# percepcao_externa_comunicacao.net
KiCad netlist of a schematic drawn in Altium Designer
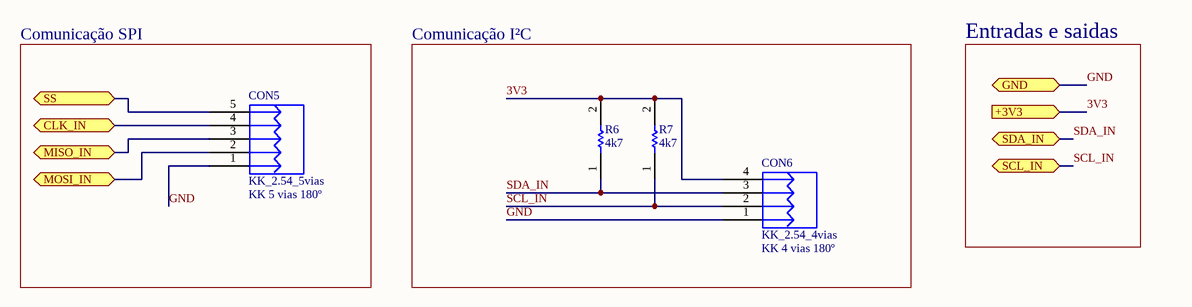
[diagram p0: percepcao_externa_comunicacao.SchDoc]

(export (version "E")
  (design (tool "Eeschema 10.0.6"))
  (components
    (comp (ref "CON5")
      (value "KK_2.54_5vias")
      (footprint "KK_5vias_180°")
      (description "Conector KK 2.54mm 5 vias")
      (fields (field (name "VALOR") "KK 5 vias 180º"))
      (libsource (lib "Sinaliza玢o_Official") (part "KK_2.54_5vias"))
    )
    (comp (ref "CON6")
      (value "KK_2.54_4vias")
      (footprint "KK_4vias_180°")
      (description "Conector KK 2.54mm 4 vias")
      (fields (field (name "VALOR") "KK 4 vias 180º"))
      (libsource (lib "Sinaliza玢o_Official") (part "KK_2.54_4vias"))
    )
    (comp (ref "R6")
      (value "4k7")
      (footprint "RESC3216X60N")
      (description "RES 1206 5%")
      (fields
        (field (name "MANUFACTURER_PART_NUMBER") "CRCW12064K70FKEA")
        (field (name "MOUSER PART NUMBER") "71-CRCW1206-4.7K-E3")
      )
      (libsource (lib "RoboHospitalar") (part "RES 1206"))
    )
    (comp (ref "R7")
      (value "4k7")
      (footprint "RESC3216X60N")
      (description "RES 1206 5%")
      (fields
        (field (name "MANUFACTURER_PART_NUMBER") "CRCW12064K70FKEA")
        (field (name "MOUSER PART NUMBER") "71-CRCW1206-4.7K-E3")
      )
      (libsource (lib "RoboHospitalar") (part "RES 1206"))
    )
  )
  (nets
    (net (code "1") (name "/3V3") (class "Default")
      (node (ref "CON6") (pin "4") (pintype "passive"))
      (node (ref "R6") (pin "2") (pinfunction "2_2") (pintype "passive"))
      (node (ref "R7") (pin "2") (pinfunction "2_2") (pintype "passive"))
    )
    (net (code "2") (name "/CLK_IN") (class "Default") (node (ref "CON5") (pin "4") (pintype "passive")))
    (net (code "3") (name "/GND") (class "Default")
      (node (ref "CON5") (pin "1") (pintype "passive"))
      (node (ref "CON6") (pin "1") (pintype "passive"))
    )
    (net (code "4") (name "/MISO_IN") (class "Default") (node (ref "CON5") (pin "3") (pintype "passive")))
    (net (code "5") (name "/MOSI_IN") (class "Default") (node (ref "CON5") (pin "2") (pintype "passive")))
    (net (code "6") (name "/SCL_IN") (class "Default")
      (node (ref "CON6") (pin "2") (pintype "passive"))
      (node (ref "R7") (pin "1") (pinfunction "1_1") (pintype "passive"))
    )
    (net (code "7") (name "/SDA_IN") (class "Default")
      (node (ref "CON6") (pin "3") (pintype "passive"))
      (node (ref "R6") (pin "1") (pinfunction "1_1") (pintype "passive"))
    )
    (net (code "8") (name "/SS") (class "Default") (node (ref "CON5") (pin "5") (pintype "passive")))
  )
)
